# schematic.net
KiCad netlist of a schematic drawn in Altium Designer
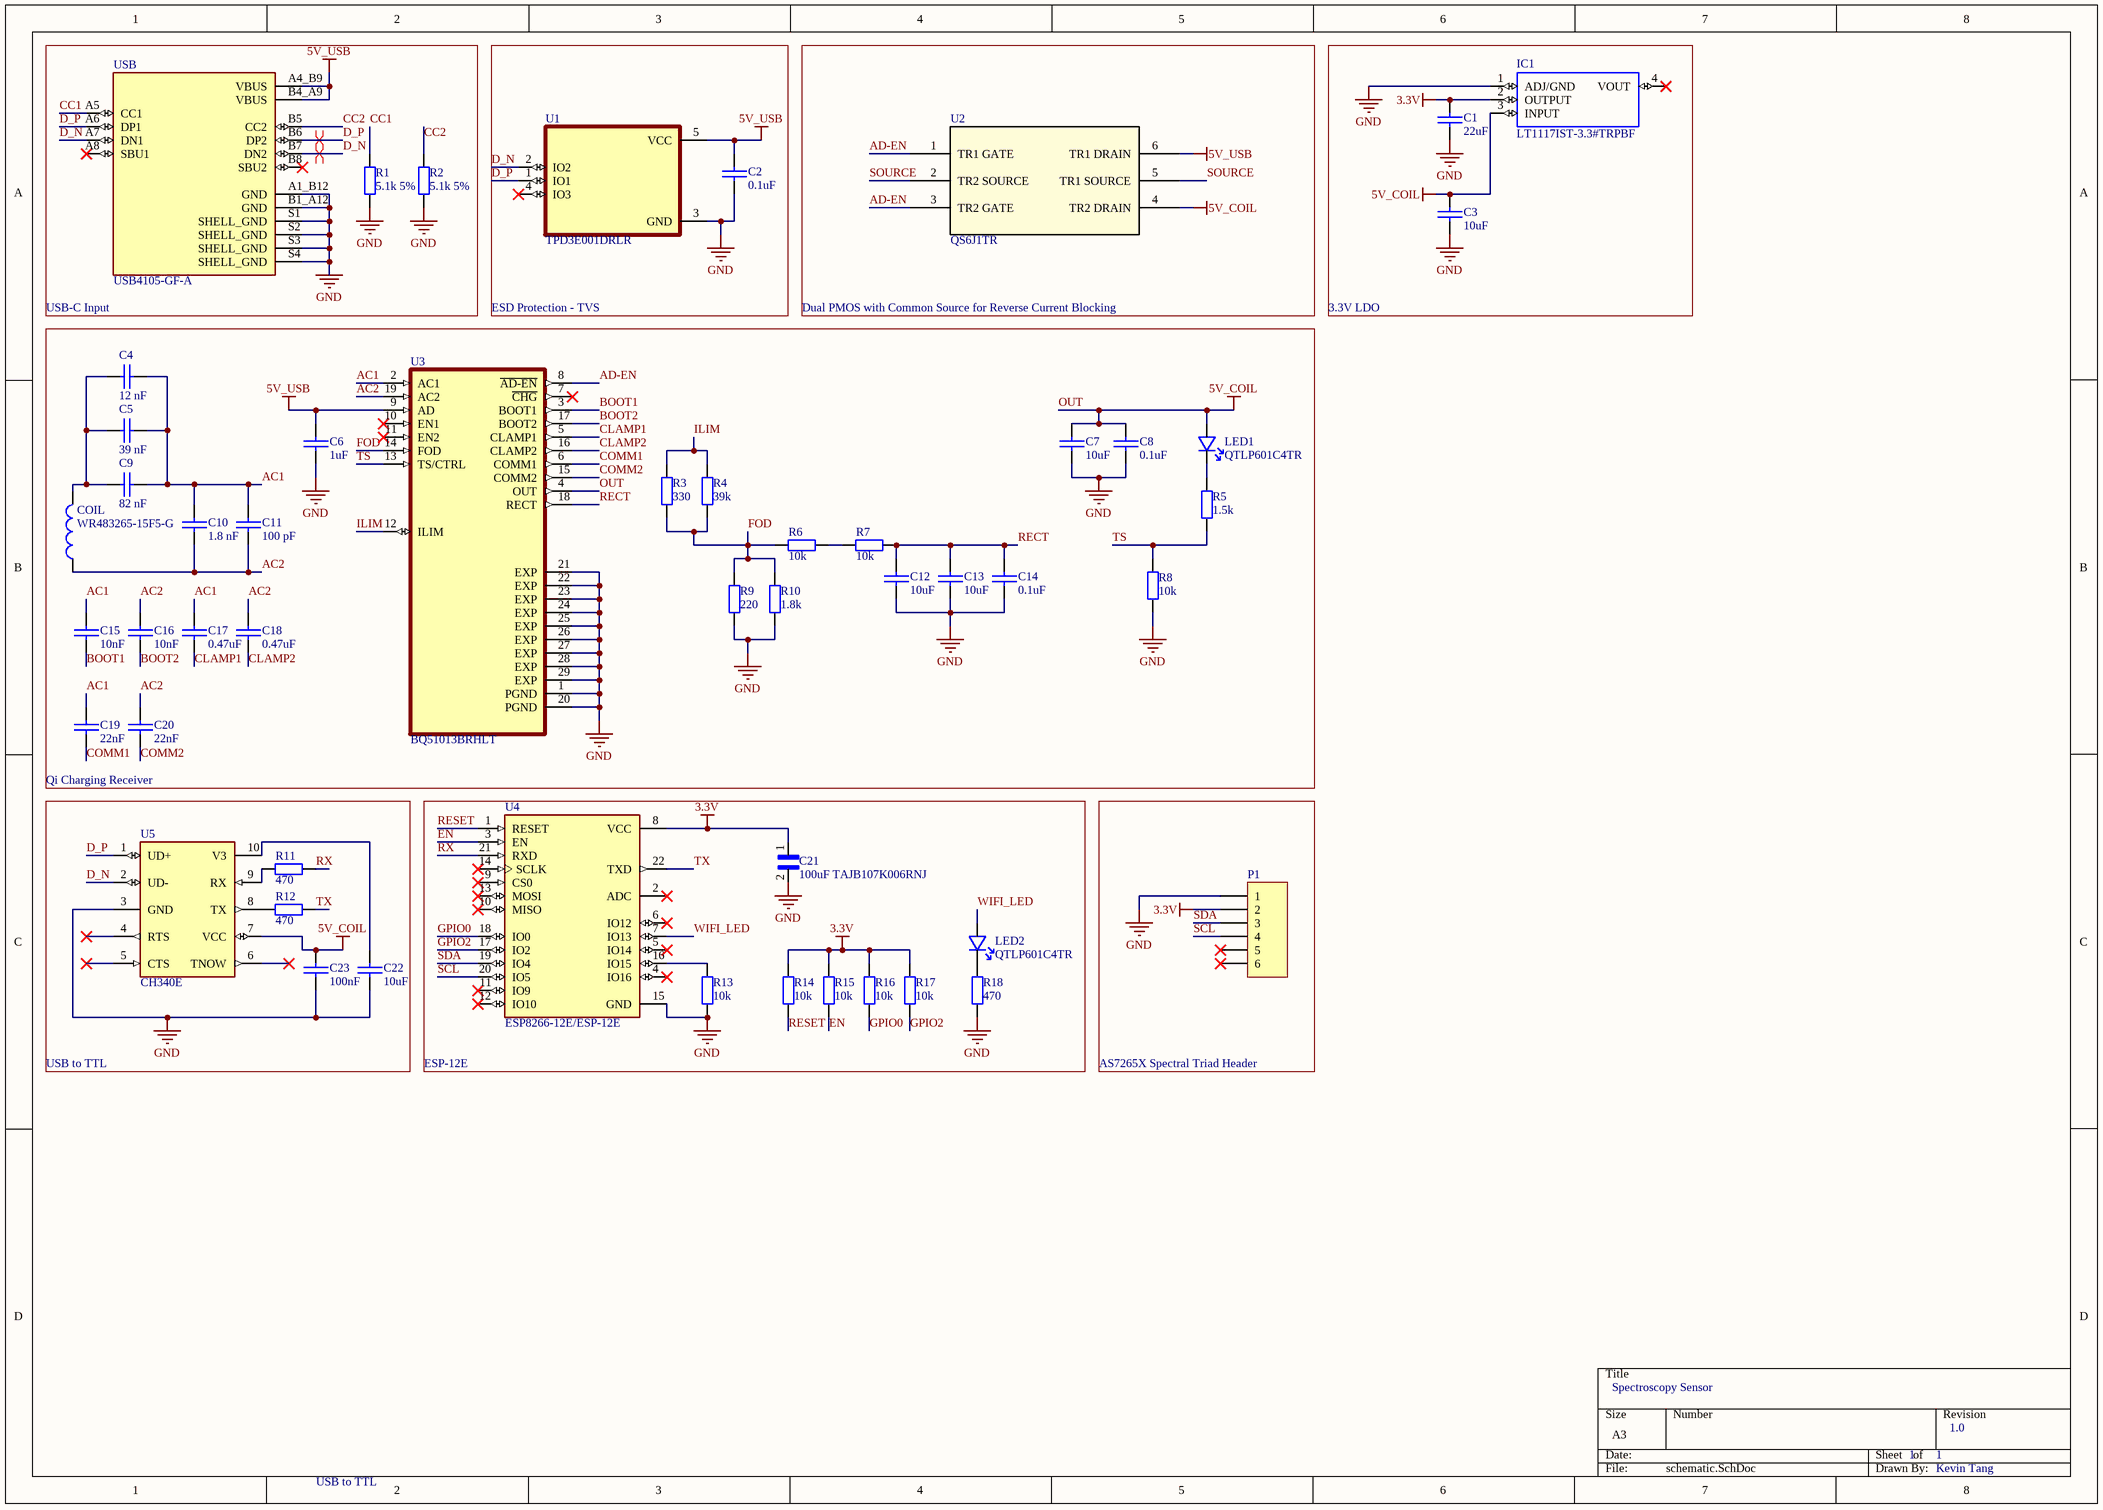
[diagram p0: schematic.SchDoc]

(export (version "E")
  (design (tool "Eeschema 10.0.6"))
  (components
    (comp (ref "C1")
      (value "22uF")
      (footprint "CAP0603")
      (description "SM capacitor")
      (libsource (lib "ece components") (part "CAP SM0603"))
    )
    (comp (ref "C2")
      (value "0.1uF")
      (footprint "CAP0603")
      (description "SM capacitor")
      (libsource (lib "ece components") (part "CAP SM0603"))
    )
    (comp (ref "C3")
      (value "10uF")
      (footprint "CAP0603")
      (description "SM capacitor")
      (libsource (lib "ece components") (part "CAP SM0603"))
    )
    (comp (ref "C4")
      (value "12 nF")
      (footprint "CAP0603")
      (description "SM capacitor")
      (libsource (lib "ece components") (part "CAP SM0603"))
    )
    (comp (ref "C5")
      (value "39 nF")
      (footprint "CAP0603")
      (description "SM capacitor")
      (libsource (lib "ece components") (part "CAP SM0603"))
    )
    (comp (ref "C6")
      (value "1uF")
      (footprint "CAP0603")
      (description "SM capacitor")
      (libsource (lib "ece components") (part "CAP SM0603"))
    )
    (comp (ref "C7")
      (value "10uF")
      (footprint "CAP0603")
      (description "SM capacitor")
      (libsource (lib "ece components") (part "CAP SM0603"))
    )
    (comp (ref "C8")
      (value "0.1uF")
      (footprint "CAP0603")
      (description "SM capacitor")
      (libsource (lib "ece components") (part "CAP SM0603"))
    )
    (comp (ref "C9")
      (value "82 nF")
      (footprint "CAP0603")
      (description "SM capacitor")
      (libsource (lib "ece components") (part "CAP SM0603"))
    )
    (comp (ref "C10")
      (value "1.8 nF")
      (footprint "CAP0603")
      (description "SM capacitor")
      (libsource (lib "ece components") (part "CAP SM0603"))
    )
    (comp (ref "C11")
      (value "100 pF")
      (footprint "CAP0603")
      (description "SM capacitor")
      (libsource (lib "ece components") (part "CAP SM0603"))
    )
    (comp (ref "C12")
      (value "10uF")
      (footprint "CAP0603")
      (description "SM capacitor")
      (libsource (lib "ece components") (part "CAP SM0603"))
    )
    (comp (ref "C13")
      (value "10uF")
      (footprint "CAP0603")
      (description "SM capacitor")
      (libsource (lib "ece components") (part "CAP SM0603"))
    )
    (comp (ref "C14")
      (value "0.1uF")
      (footprint "CAP0603")
      (description "SM capacitor")
      (libsource (lib "ece components") (part "CAP SM0603"))
    )
    (comp (ref "C15")
      (value "10nF")
      (footprint "CAP0603")
      (description "SM capacitor")
      (libsource (lib "ece components") (part "CAP SM0603"))
    )
    (comp (ref "C16")
      (value "10nF")
      (footprint "CAP0603")
      (description "SM capacitor")
      (libsource (lib "ece components") (part "CAP SM0603"))
    )
    (comp (ref "C17")
      (value "0.47uF")
      (footprint "CAP0603")
      (description "SM capacitor")
      (libsource (lib "ece components") (part "CAP SM0603"))
    )
    (comp (ref "C18")
      (value "0.47uF")
      (footprint "CAP0603")
      (description "SM capacitor")
      (libsource (lib "ece components") (part "CAP SM0603"))
    )
    (comp (ref "C19")
      (value "22nF")
      (footprint "CAP0603")
      (description "SM capacitor")
      (libsource (lib "ece components") (part "CAP SM0603"))
    )
    (comp (ref "C20")
      (value "22nF")
      (footprint "CAP0603")
      (description "SM capacitor")
      (libsource (lib "ece components") (part "CAP SM0603"))
    )
    (comp (ref "C21")
      (value "100uF TAJB107K006RNJ")
      (footprint "CAPPC3528X210N")
      (description "100ÂµF Molded Tantalum Capacitors 6.3V 1411 _3528 Metric_, 1210 1.7Ohm")
      (fields (field (name "MF") "AVX") (field (name "MP") "TAJB107K006RNJ"))
      (libsource (lib "TAJB107K006RNJ") (part "TAJB107K006RNJ"))
    )
    (comp (ref "C22")
      (value "10uF")
      (footprint "CAP0603")
      (description "SM capacitor")
      (libsource (lib "ece components") (part "CAP SM0603"))
    )
    (comp (ref "C23")
      (value "100nF")
      (footprint "CAP0603")
      (description "SM capacitor")
      (libsource (lib "ece components") (part "CAP SM0603"))
    )
    (comp (ref "COIL")
      (value "WR483265-15F5-G")
      (footprint "ece-INDUCTOR1005")
      (description "inductor Surface Mount")
      (libsource (lib "ece components") (part "Inductor"))
    )
    (comp (ref "IC1")
      (value "LT1117IST-3.3#TRPBF")
      (footprint "SOT230P700X170-4N")
      (description "Linear Voltage Regulator IC Positive Fixed 1 Output 1A SOT-223")
      (fields (field (name "MF") "Diodes Inc.") (field (name "MP") "AZ1117IH-3.3TRG1"))
      (libsource (lib "AZ1117IH-3.3TRG1") (part "AZ1117IH-3.3TRG1"))
    )
    (comp (ref "LED1")
      (value "QTLP601C4TR")
      (footprint "LED0603P")
      (description "LED SM 0603 GREEN 1V95 FWD VOLTAGE")
      (libsource (lib "electronpowered") (part "LNJ337W83RA"))
    )
    (comp (ref "LED2")
      (value "QTLP601C4TR")
      (footprint "LED0603P")
      (description "LED SM 0603 GREEN 1V95 FWD VOLTAGE")
      (libsource (lib "electronpowered") (part "LNJ337W83RA"))
    )
    (comp (ref "P1")
      (value "Header 6")
      (footprint "ece-HDR1X6")
      (description "Header, 6-Pin")
      (fields (field (name "PUBLISHER") "Altium Limited"))
      (libsource (lib "ece components") (part "Header 6"))
    )
    (comp (ref "R1")
      (value "5.1k 5%")
      (footprint "RES0603")
      (description "Resistor")
      (libsource (lib "ece components") (part "Res SM 0603"))
    )
    (comp (ref "R2")
      (value "5.1k 5%")
      (footprint "RES0603")
      (description "Resistor")
      (libsource (lib "ece components") (part "Res SM 0603"))
    )
    (comp (ref "R3")
      (value "330")
      (footprint "RES0603")
      (description "Resistor")
      (libsource (lib "ece components") (part "Res SM 0603"))
    )
    (comp (ref "R4")
      (value "39k")
      (footprint "RES0603")
      (description "Resistor")
      (libsource (lib "ece components") (part "Res SM 0603"))
    )
    (comp (ref "R5")
      (value "1.5k")
      (footprint "RES0603")
      (description "Resistor")
      (libsource (lib "ece components") (part "Res SM 0603"))
    )
    (comp (ref "R6")
      (value "10k")
      (footprint "RES0603")
      (description "Resistor")
      (libsource (lib "") (part "Res SM 0603_1"))
    )
    (comp (ref "R7")
      (value "10k")
      (footprint "RES0603")
      (description "Resistor")
      (libsource (lib "") (part "Res SM 0603_1"))
    )
    (comp (ref "R8")
      (value "10k")
      (footprint "RES0603")
      (description "Resistor")
      (libsource (lib "ece components") (part "Res SM 0603"))
    )
    (comp (ref "R9")
      (value "220")
      (footprint "RES0603")
      (description "Resistor")
      (libsource (lib "ece components") (part "Res SM 0603"))
    )
    (comp (ref "R10")
      (value "1.8k")
      (footprint "RES0603")
      (description "Resistor")
      (libsource (lib "ece components") (part "Res SM 0603"))
    )
    (comp (ref "R11")
      (value "470")
      (footprint "RES0603")
      (description "Resistor")
      (libsource (lib "") (part "Res SM 0603_1"))
    )
    (comp (ref "R12")
      (value "470")
      (footprint "RES0603")
      (description "Resistor")
      (libsource (lib "") (part "Res SM 0603_1"))
    )
    (comp (ref "R13")
      (value "10k")
      (footprint "RES0603")
      (description "Resistor")
      (libsource (lib "ece components") (part "Res SM 0603"))
    )
    (comp (ref "R14")
      (value "10k")
      (footprint "RES0603")
      (description "Resistor")
      (libsource (lib "ece components") (part "Res SM 0603"))
    )
    (comp (ref "R15")
      (value "10k")
      (footprint "RES0603")
      (description "Resistor")
      (libsource (lib "ece components") (part "Res SM 0603"))
    )
    (comp (ref "R16")
      (value "10k")
      (footprint "RES0603")
      (description "Resistor")
      (libsource (lib "ece components") (part "Res SM 0603"))
    )
    (comp (ref "R17")
      (value "10k")
      (footprint "RES0603")
      (description "Resistor")
      (libsource (lib "ece components") (part "Res SM 0603"))
    )
    (comp (ref "R18")
      (value "470")
      (footprint "RES0603")
      (description "Resistor")
      (libsource (lib "") (part "Res SM 0603_2"))
    )
    (comp (ref "U1")
      (value "TPD3E001DRLR")
      (footprint "SOT50P160X60-5N")
      (fields (field (name "DIGI-KEY_PART_NUMBER") "296-21885-1-ND") (field (name "MF") "Texas Instruments"))
      (libsource (lib "TPD3E001DRLR") (part "TPD3E001DRLR"))
    )
    (comp (ref "U2")
      (value "QS6J1TR")
      (footprint "TRANS_QS6_ROM")
      (description "No Description Available")
      (fields (field (name "COPYRIGHT") "Copyright (C) 2018 Accelerated Designs. All rights reserved"))
      (libsource (lib "QS6J1TR") (part "QS6J1TR"))
    )
    (comp (ref "U3")
      (value "BQ51013BRHLT")
      (footprint "IC_MSP430FR2522IRHLR")
      (description "WPC 1.1 Compatible Fully integrated Wireless power Receiver IC 20-VQFN 0 to 125")
      (fields (field (name "DIGI-KEY_PART_NUMBER") "296-35638-1-ND") (field (name "MF") "Texas Instruments"))
      (libsource (lib "BQ51013BRHLT") (part "BQ51013BRHLT"))
    )
    (comp (ref "U4")
      (value "ESP8266-12E/ESP-12E")
      (footprint "XCVR_ESP8266-12E/ESP-12E")
      (fields (field (name "MF") "AI-Thinker"))
      (libsource (lib "ESP8266-12E_ESP-12E") (part "ESP8266-12E/ESP-12E"))
    )
    (comp (ref "U5")
      (value "CH340E")
      (footprint "MSOP10")
      (description "USB to serial chip CH340")
      (fields (field (name "MF") "WCH"))
      (libsource (lib "CH340E_v2") (part "CH340E"))
    )
    (comp (ref "USB")
      (value "USB4105-GF-A")
      (footprint "GCT_USB4105-GF-A")
      (fields (field (name "MF") "GCT"))
      (libsource (lib "USB4105-GF-A") (part "USB4105-GF-A"))
    )
  )
  (nets
    (net (code "1") (name "/AC1") (class "Default")
      (node (ref "C10") (pin "1") (pinfunction "1_1") (pintype "passive"))
      (node (ref "C11") (pin "1") (pinfunction "1_1") (pintype "passive"))
      (node (ref "C15") (pin "1") (pinfunction "1_1") (pintype "passive"))
      (node (ref "C17") (pin "1") (pinfunction "1_1") (pintype "passive"))
      (node (ref "C19") (pin "1") (pinfunction "1_1") (pintype "passive"))
      (node (ref "C4") (pin "2") (pinfunction "2_2") (pintype "passive"))
      (node (ref "C5") (pin "2") (pinfunction "2_2") (pintype "passive"))
      (node (ref "C9") (pin "2") (pinfunction "2_2") (pintype "passive"))
      (node (ref "U3") (pin "2") (pinfunction "AC1_2") (pintype "input"))
    )
    (net (code "2") (name "/AC2") (class "Default")
      (node (ref "C10") (pin "2") (pinfunction "2_2") (pintype "passive"))
      (node (ref "C11") (pin "2") (pinfunction "2_2") (pintype "passive"))
      (node (ref "C16") (pin "1") (pinfunction "1_1") (pintype "passive"))
      (node (ref "C18") (pin "1") (pinfunction "1_1") (pintype "passive"))
      (node (ref "C20") (pin "1") (pinfunction "1_1") (pintype "passive"))
      (node (ref "COIL") (pin "1") (pinfunction "1_1") (pintype "passive"))
      (node (ref "U3") (pin "19") (pinfunction "AC2_19") (pintype "input"))
    )
    (net (code "3") (name "/AD-EN") (class "Default")
      (node (ref "U2") (pin "1") (pinfunction "TR1_GATE_1") (pintype "passive"))
      (node (ref "U2") (pin "3") (pinfunction "TR2_GATE_3") (pintype "passive"))
      (node (ref "U3") (pin "8") (pinfunction "~{AD-EN}_8") (pintype "output"))
    )
    (net (code "4") (name "/BOOT1") (class "Default")
      (node (ref "C15") (pin "2") (pinfunction "2_2") (pintype "passive"))
      (node (ref "U3") (pin "3") (pinfunction "BOOT1_3") (pintype "output"))
    )
    (net (code "5") (name "/BOOT2") (class "Default")
      (node (ref "C16") (pin "2") (pinfunction "2_2") (pintype "passive"))
      (node (ref "U3") (pin "17") (pinfunction "BOOT2_17") (pintype "output"))
    )
    (net (code "6") (name "/CC1") (class "Default")
      (node (ref "R1") (pin "2") (pinfunction "2_2") (pintype "passive"))
      (node (ref "USB") (pin "A5") (pinfunction "CC1_A5") (pintype "bidirectional"))
    )
    (net (code "7") (name "/CC2") (class "Default")
      (node (ref "R2") (pin "2") (pinfunction "2_2") (pintype "passive"))
      (node (ref "USB") (pin "B5") (pinfunction "CC2_B5") (pintype "bidirectional"))
    )
    (net (code "8") (name "/CLAMP1") (class "Default")
      (node (ref "C17") (pin "2") (pinfunction "2_2") (pintype "passive"))
      (node (ref "U3") (pin "5") (pinfunction "CLAMP1_5") (pintype "output"))
    )
    (net (code "9") (name "/CLAMP2") (class "Default")
      (node (ref "C18") (pin "2") (pinfunction "2_2") (pintype "passive"))
      (node (ref "U3") (pin "16") (pinfunction "CLAMP2_16") (pintype "output"))
    )
    (net (code "10") (name "/COMM1") (class "Default")
      (node (ref "C19") (pin "2") (pinfunction "2_2") (pintype "passive"))
      (node (ref "U3") (pin "6") (pinfunction "COMM1_6") (pintype "output"))
    )
    (net (code "11") (name "/COMM2") (class "Default")
      (node (ref "C20") (pin "2") (pinfunction "2_2") (pintype "passive"))
      (node (ref "U3") (pin "15") (pinfunction "COMM2_15") (pintype "output"))
    )
    (net (code "12") (name "/D_N") (class "Default")
      (node (ref "U1") (pin "2") (pinfunction "IO2_2") (pintype "bidirectional"))
      (node (ref "U5") (pin "2") (pinfunction "UD-_2") (pintype "bidirectional"))
      (node (ref "USB") (pin "A7") (pinfunction "DN1_A7") (pintype "bidirectional"))
      (node (ref "USB") (pin "B7") (pinfunction "DN2_B7") (pintype "bidirectional"))
    )
    (net (code "13") (name "/D_P") (class "Default")
      (node (ref "U1") (pin "1") (pinfunction "IO1_1") (pintype "bidirectional"))
      (node (ref "U5") (pin "1") (pinfunction "UD+_1") (pintype "bidirectional"))
      (node (ref "USB") (pin "A6") (pinfunction "DP1_A6") (pintype "bidirectional"))
      (node (ref "USB") (pin "B6") (pinfunction "DP2_B6") (pintype "bidirectional"))
    )
    (net (code "14") (name "/EN") (class "Default")
      (node (ref "R15") (pin "1") (pinfunction "1_1") (pintype "passive"))
      (node (ref "U4") (pin "3") (pinfunction "EN_3") (pintype "input"))
    )
    (net (code "15") (name "/FOD") (class "Default")
      (node (ref "R10") (pin "2") (pinfunction "2_2") (pintype "passive"))
      (node (ref "R3") (pin "1") (pinfunction "1_1") (pintype "passive"))
      (node (ref "R4") (pin "1") (pinfunction "1_1") (pintype "passive"))
      (node (ref "R6") (pin "1") (pinfunction "1_1") (pintype "passive"))
      (node (ref "R9") (pin "2") (pinfunction "2_2") (pintype "passive"))
      (node (ref "U3") (pin "14") (pinfunction "FOD_14") (pintype "input"))
    )
    (net (code "16") (name "/GPIO0") (class "Default")
      (node (ref "R16") (pin "1") (pinfunction "1_1") (pintype "passive"))
      (node (ref "U4") (pin "18") (pinfunction "IO0_18") (pintype "bidirectional"))
    )
    (net (code "17") (name "/GPIO2") (class "Default")
      (node (ref "R17") (pin "1") (pinfunction "1_1") (pintype "passive"))
      (node (ref "U4") (pin "17") (pinfunction "IO2_17") (pintype "bidirectional"))
    )
    (net (code "18") (name "/ILIM") (class "Default")
      (node (ref "R3") (pin "2") (pinfunction "2_2") (pintype "passive"))
      (node (ref "R4") (pin "2") (pinfunction "2_2") (pintype "passive"))
      (node (ref "U3") (pin "12") (pinfunction "ILIM_12") (pintype "bidirectional"))
    )
    (net (code "19") (name "/RECT") (class "Default")
      (node (ref "C12") (pin "1") (pinfunction "1_1") (pintype "passive"))
      (node (ref "C13") (pin "1") (pinfunction "1_1") (pintype "passive"))
      (node (ref "C14") (pin "1") (pinfunction "1_1") (pintype "passive"))
      (node (ref "R7") (pin "2") (pinfunction "2_2") (pintype "passive"))
      (node (ref "U3") (pin "18") (pinfunction "RECT_18") (pintype "output"))
    )
    (net (code "20") (name "/RESET") (class "Default")
      (node (ref "R14") (pin "1") (pinfunction "1_1") (pintype "passive"))
      (node (ref "U4") (pin "1") (pinfunction "RESET_1") (pintype "input"))
    )
    (net (code "21") (name "/RX") (class "Default")
      (node (ref "R11") (pin "2") (pinfunction "2_2") (pintype "passive"))
      (node (ref "U4") (pin "21") (pinfunction "RXD_21") (pintype "input"))
    )
    (net (code "22") (name "/SCL") (class "Default")
      (node (ref "P1") (pin "4") (pinfunction "4_4") (pintype "passive"))
      (node (ref "U4") (pin "20") (pinfunction "IO5_20") (pintype "bidirectional"))
    )
    (net (code "23") (name "/SDA") (class "Default")
      (node (ref "P1") (pin "3") (pinfunction "3_3") (pintype "passive"))
      (node (ref "U4") (pin "19") (pinfunction "IO4_19") (pintype "bidirectional"))
    )
    (net (code "24") (name "/SOURCE") (class "Default")
      (node (ref "U2") (pin "2") (pinfunction "TR2_SOURCE_2") (pintype "passive"))
      (node (ref "U2") (pin "5") (pinfunction "TR1_SOURCE_5") (pintype "passive"))
    )
    (net (code "25") (name "/TS") (class "Default")
      (node (ref "R5") (pin "1") (pinfunction "1_1") (pintype "passive"))
      (node (ref "R8") (pin "2") (pinfunction "2_2") (pintype "passive"))
      (node (ref "U3") (pin "13") (pinfunction "TS/CTRL_13") (pintype "input"))
    )
    (net (code "26") (name "/TX") (class "Default")
      (node (ref "R12") (pin "2") (pinfunction "2_2") (pintype "passive"))
      (node (ref "U4") (pin "22") (pinfunction "TXD_22") (pintype "output"))
    )
    (net (code "27") (name "/WIFI_LED") (class "Default")
      (node (ref "LED2") (pin "1") (pinfunction "1_1") (pintype "passive"))
      (node (ref "U4") (pin "7") (pinfunction "IO13_7") (pintype "bidirectional"))
    )
    (net (code "28") (name "3.3V") (class "Default")
      (node (ref "C1") (pin "1") (pinfunction "1_1") (pintype "passive"))
      (node (ref "C21") (pin "1") (pinfunction "1_1") (pintype "passive"))
      (node (ref "IC1") (pin "2") (pinfunction "OUTPUT_2") (pintype "bidirectional"))
      (node (ref "P1") (pin "2") (pinfunction "2_2") (pintype "passive"))
      (node (ref "R14") (pin "2") (pinfunction "2_2") (pintype "passive"))
      (node (ref "R15") (pin "2") (pinfunction "2_2") (pintype "passive"))
      (node (ref "R16") (pin "2") (pinfunction "2_2") (pintype "passive"))
      (node (ref "R17") (pin "2") (pinfunction "2_2") (pintype "passive"))
      (node (ref "U4") (pin "8") (pinfunction "VCC_8") (pintype "power_in"))
    )
    (net (code "29") (name "5V_COIL") (class "Default")
      (node (ref "C23") (pin "1") (pinfunction "1_1") (pintype "passive"))
      (node (ref "C3") (pin "1") (pinfunction "1_1") (pintype "passive"))
      (node (ref "C7") (pin "1") (pinfunction "1_1") (pintype "passive"))
      (node (ref "C8") (pin "1") (pinfunction "1_1") (pintype "passive"))
      (node (ref "IC1") (pin "3") (pinfunction "INPUT_3") (pintype "bidirectional"))
      (node (ref "LED1") (pin "1") (pinfunction "1_1") (pintype "passive"))
      (node (ref "U2") (pin "4") (pinfunction "TR2_DRAIN_4") (pintype "passive"))
      (node (ref "U3") (pin "4") (pinfunction "OUT_4") (pintype "output"))
      (node (ref "U5") (pin "7") (pinfunction "VCC_7") (pintype "bidirectional"))
    )
    (net (code "30") (name "5V_USB") (class "Default")
      (node (ref "C2") (pin "1") (pinfunction "1_1") (pintype "passive"))
      (node (ref "C6") (pin "1") (pinfunction "1_1") (pintype "passive"))
      (node (ref "U1") (pin "5") (pinfunction "VCC_5") (pintype "power_in"))
      (node (ref "U2") (pin "6") (pinfunction "TR1_DRAIN_6") (pintype "passive"))
      (node (ref "U3") (pin "9") (pinfunction "AD_9") (pintype "input"))
      (node (ref "USB") (pin "A4_B9") (pinfunction "VBUS_A4_B9") (pintype "power_in"))
      (node (ref "USB") (pin "B4_A9") (pinfunction "VBUS_B4_A9") (pintype "power_in"))
    )
    (net (code "31") (name "GND") (class "Default")
      (node (ref "C1") (pin "2") (pinfunction "2_2") (pintype "passive"))
      (node (ref "C12") (pin "2") (pinfunction "2_2") (pintype "passive"))
      (node (ref "C13") (pin "2") (pinfunction "2_2") (pintype "passive"))
      (node (ref "C14") (pin "2") (pinfunction "2_2") (pintype "passive"))
      (node (ref "C2") (pin "2") (pinfunction "2_2") (pintype "passive"))
      (node (ref "C21") (pin "2") (pinfunction "2_2") (pintype "passive"))
      (node (ref "C22") (pin "2") (pinfunction "2_2") (pintype "passive"))
      (node (ref "C23") (pin "2") (pinfunction "2_2") (pintype "passive"))
      (node (ref "C3") (pin "2") (pinfunction "2_2") (pintype "passive"))
      (node (ref "C6") (pin "2") (pinfunction "2_2") (pintype "passive"))
      (node (ref "C7") (pin "2") (pinfunction "2_2") (pintype "passive"))
      (node (ref "C8") (pin "2") (pinfunction "2_2") (pintype "passive"))
      (node (ref "IC1") (pin "1") (pinfunction "ADJ/GND_1") (pintype "bidirectional"))
      (node (ref "P1") (pin "1") (pinfunction "1_1") (pintype "passive"))
      (node (ref "R1") (pin "1") (pinfunction "1_1") (pintype "passive"))
      (node (ref "R10") (pin "1") (pinfunction "1_1") (pintype "passive"))
      (node (ref "R13") (pin "1") (pinfunction "1_1") (pintype "passive"))
      (node (ref "R18") (pin "2") (pinfunction "2_2") (pintype "passive"))
      (node (ref "R2") (pin "1") (pinfunction "1_1") (pintype "passive"))
      (node (ref "R8") (pin "1") (pinfunction "1_1") (pintype "passive"))
      (node (ref "R9") (pin "1") (pinfunction "1_1") (pintype "passive"))
      (node (ref "U1") (pin "3") (pinfunction "GND_3") (pintype "power_in"))
      (node (ref "U3") (pin "1") (pinfunction "PGND_1") (pintype "power_in"))
      (node (ref "U3") (pin "20") (pinfunction "PGND_20") (pintype "power_in"))
      (node (ref "U3") (pin "21") (pinfunction "EXP_21") (pintype "power_in"))
      (node (ref "U3") (pin "22") (pinfunction "EXP_22") (pintype "power_in"))
      (node (ref "U3") (pin "23") (pinfunction "EXP_23") (pintype "power_in"))
      (node (ref "U3") (pin "24") (pinfunction "EXP_24") (pintype "power_in"))
      (node (ref "U3") (pin "25") (pinfunction "EXP_25") (pintype "power_in"))
      (node (ref "U3") (pin "26") (pinfunction "EXP_26") (pintype "power_in"))
      (node (ref "U3") (pin "27") (pinfunction "EXP_27") (pintype "power_in"))
      (node (ref "U3") (pin "28") (pinfunction "EXP_28") (pintype "power_in"))
      (node (ref "U3") (pin "29") (pinfunction "EXP_29") (pintype "power_in"))
      (node (ref "U4") (pin "15") (pinfunction "GND_15") (pintype "power_in"))
      (node (ref "U5") (pin "3") (pinfunction "GND_3") (pintype "power_in"))
      (node (ref "USB") (pin "A1_B12") (pinfunction "GND_A1_B12") (pintype "power_in"))
      (node (ref "USB") (pin "B1_A12") (pinfunction "GND_B1_A12") (pintype "power_in"))
      (node (ref "USB") (pin "S1") (pinfunction "SHELL_GND_S1") (pintype "power_in"))
      (node (ref "USB") (pin "S2") (pinfunction "SHELL_GND_S2") (pintype "power_in"))
      (node (ref "USB") (pin "S3") (pinfunction "SHELL_GND_S3") (pintype "power_in"))
      (node (ref "USB") (pin "S4") (pinfunction "SHELL_GND_S4") (pintype "power_in"))
    )
    (net (code "32") (name "Net-(C4-Pad1)") (class "Default")
      (node (ref "C4") (pin "1") (pinfunction "1_1") (pintype "passive"))
      (node (ref "C5") (pin "1") (pinfunction "1_1") (pintype "passive"))
      (node (ref "C9") (pin "1") (pinfunction "1_1") (pintype "passive"))
      (node (ref "COIL") (pin "2") (pinfunction "2_2") (pintype "passive"))
    )
    (net (code "33") (name "Net-(LED1-Pad2)") (class "Default")
      (node (ref "LED1") (pin "2") (pinfunction "2_2") (pintype "passive"))
      (node (ref "R5") (pin "2") (pinfunction "2_2") (pintype "passive"))
    )
    (net (code "34") (name "Net-(LED2-Pad2)") (class "Default")
      (node (ref "LED2") (pin "2") (pinfunction "2_2") (pintype "passive"))
      (node (ref "R18") (pin "1") (pinfunction "1_1") (pintype "passive"))
    )
    (net (code "35") (name "Net-(R6-Pad2)") (class "Default")
      (node (ref "R6") (pin "2") (pinfunction "2_2") (pintype "passive"))
      (node (ref "R7") (pin "1") (pinfunction "1_1") (pintype "passive"))
    )
    (net (code "36") (name "Net-(U4-IO15)") (class "Default")
      (node (ref "R13") (pin "2") (pinfunction "2_2") (pintype "passive"))
      (node (ref "U4") (pin "16") (pinfunction "IO15_16") (pintype "bidirectional"))
    )
    (net (code "37") (name "Net-(U5-RX)") (class "Default")
      (node (ref "R11") (pin "1") (pinfunction "1_1") (pintype "passive"))
      (node (ref "U5") (pin "9") (pinfunction "RX_9") (pintype "input"))
    )
    (net (code "38") (name "Net-(U5-TX)") (class "Default")
      (node (ref "R12") (pin "1") (pinfunction "1_1") (pintype "passive"))
      (node (ref "U5") (pin "8") (pinfunction "TX_8") (pintype "output"))
    )
    (net (code "39") (name "Net-(U5-V3)") (class "Default")
      (node (ref "C22") (pin "1") (pinfunction "1_1") (pintype "passive"))
      (node (ref "U5") (pin "10") (pinfunction "V3_10") (pintype "power_in"))
    )
    (net (code "40") (name "unconnected-(IC1-VOUT-Pad4)") (class "Default")
      (node (ref "IC1") (pin "4") (pinfunction "VOUT_4") (pintype "bidirectional+no_connect"))
    )
    (net (code "41") (name "unconnected-(P1-Pad5)") (class "Default")
      (node (ref "P1") (pin "5") (pinfunction "5_5") (pintype "passive+no_connect"))
    )
    (net (code "42") (name "unconnected-(P1-Pad6)") (class "Default")
      (node (ref "P1") (pin "6") (pinfunction "6_6") (pintype "passive+no_connect"))
    )
    (net (code "43") (name "unconnected-(U1-IO3-Pad4)") (class "Default")
      (node (ref "U1") (pin "4") (pinfunction "IO3_4") (pintype "bidirectional+no_connect"))
    )
    (net (code "44") (name "unconnected-(U3-EN1-Pad10)") (class "Default")
      (node (ref "U3") (pin "10") (pinfunction "EN1_10") (pintype "input+no_connect"))
    )
    (net (code "45") (name "unconnected-(U3-EN2-Pad11)") (class "Default")
      (node (ref "U3") (pin "11") (pinfunction "EN2_11") (pintype "input+no_connect"))
    )
    (net (code "46") (name "unconnected-(U3-~{CHG}-Pad7)") (class "Default")
      (node (ref "U3") (pin "7") (pinfunction "~{CHG}_7") (pintype "output+no_connect"))
    )
    (net (code "47") (name "unconnected-(U4-ADC-Pad2)") (class "Default")
      (node (ref "U4") (pin "2") (pinfunction "ADC_2") (pintype "passive+no_connect"))
    )
    (net (code "48") (name "unconnected-(U4-CS0-Pad9)") (class "Default")
      (node (ref "U4") (pin "9") (pinfunction "CS0_9") (pintype "input+no_connect"))
    )
    (net (code "49") (name "unconnected-(U4-IO9-Pad11)") (class "Default")
      (node (ref "U4") (pin "11") (pinfunction "IO9_11") (pintype "bidirectional+no_connect"))
    )
    (net (code "50") (name "unconnected-(U4-IO10-Pad12)") (class "Default")
      (node (ref "U4") (pin "12") (pinfunction "IO10_12") (pintype "bidirectional+no_connect"))
    )
    (net (code "51") (name "unconnected-(U4-IO12-Pad6)") (class "Default")
      (node (ref "U4") (pin "6") (pinfunction "IO12_6") (pintype "bidirectional+no_connect"))
    )
    (net (code "52") (name "unconnected-(U4-IO14-Pad5)") (class "Default")
      (node (ref "U4") (pin "5") (pinfunction "IO14_5") (pintype "bidirectional+no_connect"))
    )
    (net (code "53") (name "unconnected-(U4-IO16-Pad4)") (class "Default")
      (node (ref "U4") (pin "4") (pinfunction "IO16_4") (pintype "bidirectional+no_connect"))
    )
    (net (code "54") (name "unconnected-(U4-MISO-Pad10)") (class "Default")
      (node (ref "U4") (pin "10") (pinfunction "MISO_10") (pintype "bidirectional+no_connect"))
    )
    (net (code "55") (name "unconnected-(U4-MOSI-Pad13)") (class "Default")
      (node (ref "U4") (pin "13") (pinfunction "MOSI_13") (pintype "bidirectional+no_connect"))
    )
    (net (code "56") (name "unconnected-(U4-SCLK-Pad14)") (class "Default")
      (node (ref "U4") (pin "14") (pinfunction "SCLK_14") (pintype "input+no_connect"))
    )
    (net (code "57") (name "unconnected-(U5-CTS-Pad5)") (class "Default")
      (node (ref "U5") (pin "5") (pinfunction "CTS_5") (pintype "input+no_connect"))
    )
    (net (code "58") (name "unconnected-(U5-RTS-Pad4)") (class "Default")
      (node (ref "U5") (pin "4") (pinfunction "RTS_4") (pintype "output+no_connect"))
    )
    (net (code "59") (name "unconnected-(U5-TNOW-Pad6)") (class "Default")
      (node (ref "U5") (pin "6") (pinfunction "TNOW_6") (pintype "output+no_connect"))
    )
    (net (code "60") (name "unconnected-(USB-SBU1-PadA8)") (class "Default")
      (node (ref "USB") (pin "A8") (pinfunction "SBU1_A8") (pintype "bidirectional+no_connect"))
    )
    (net (code "61") (name "unconnected-(USB-SBU2-PadB8)") (class "Default")
      (node (ref "USB") (pin "B8") (pinfunction "SBU2_B8") (pintype "bidirectional+no_connect"))
    )
  )
)
